# charging_block.net
KiCad netlist of a schematic drawn in EAGLE
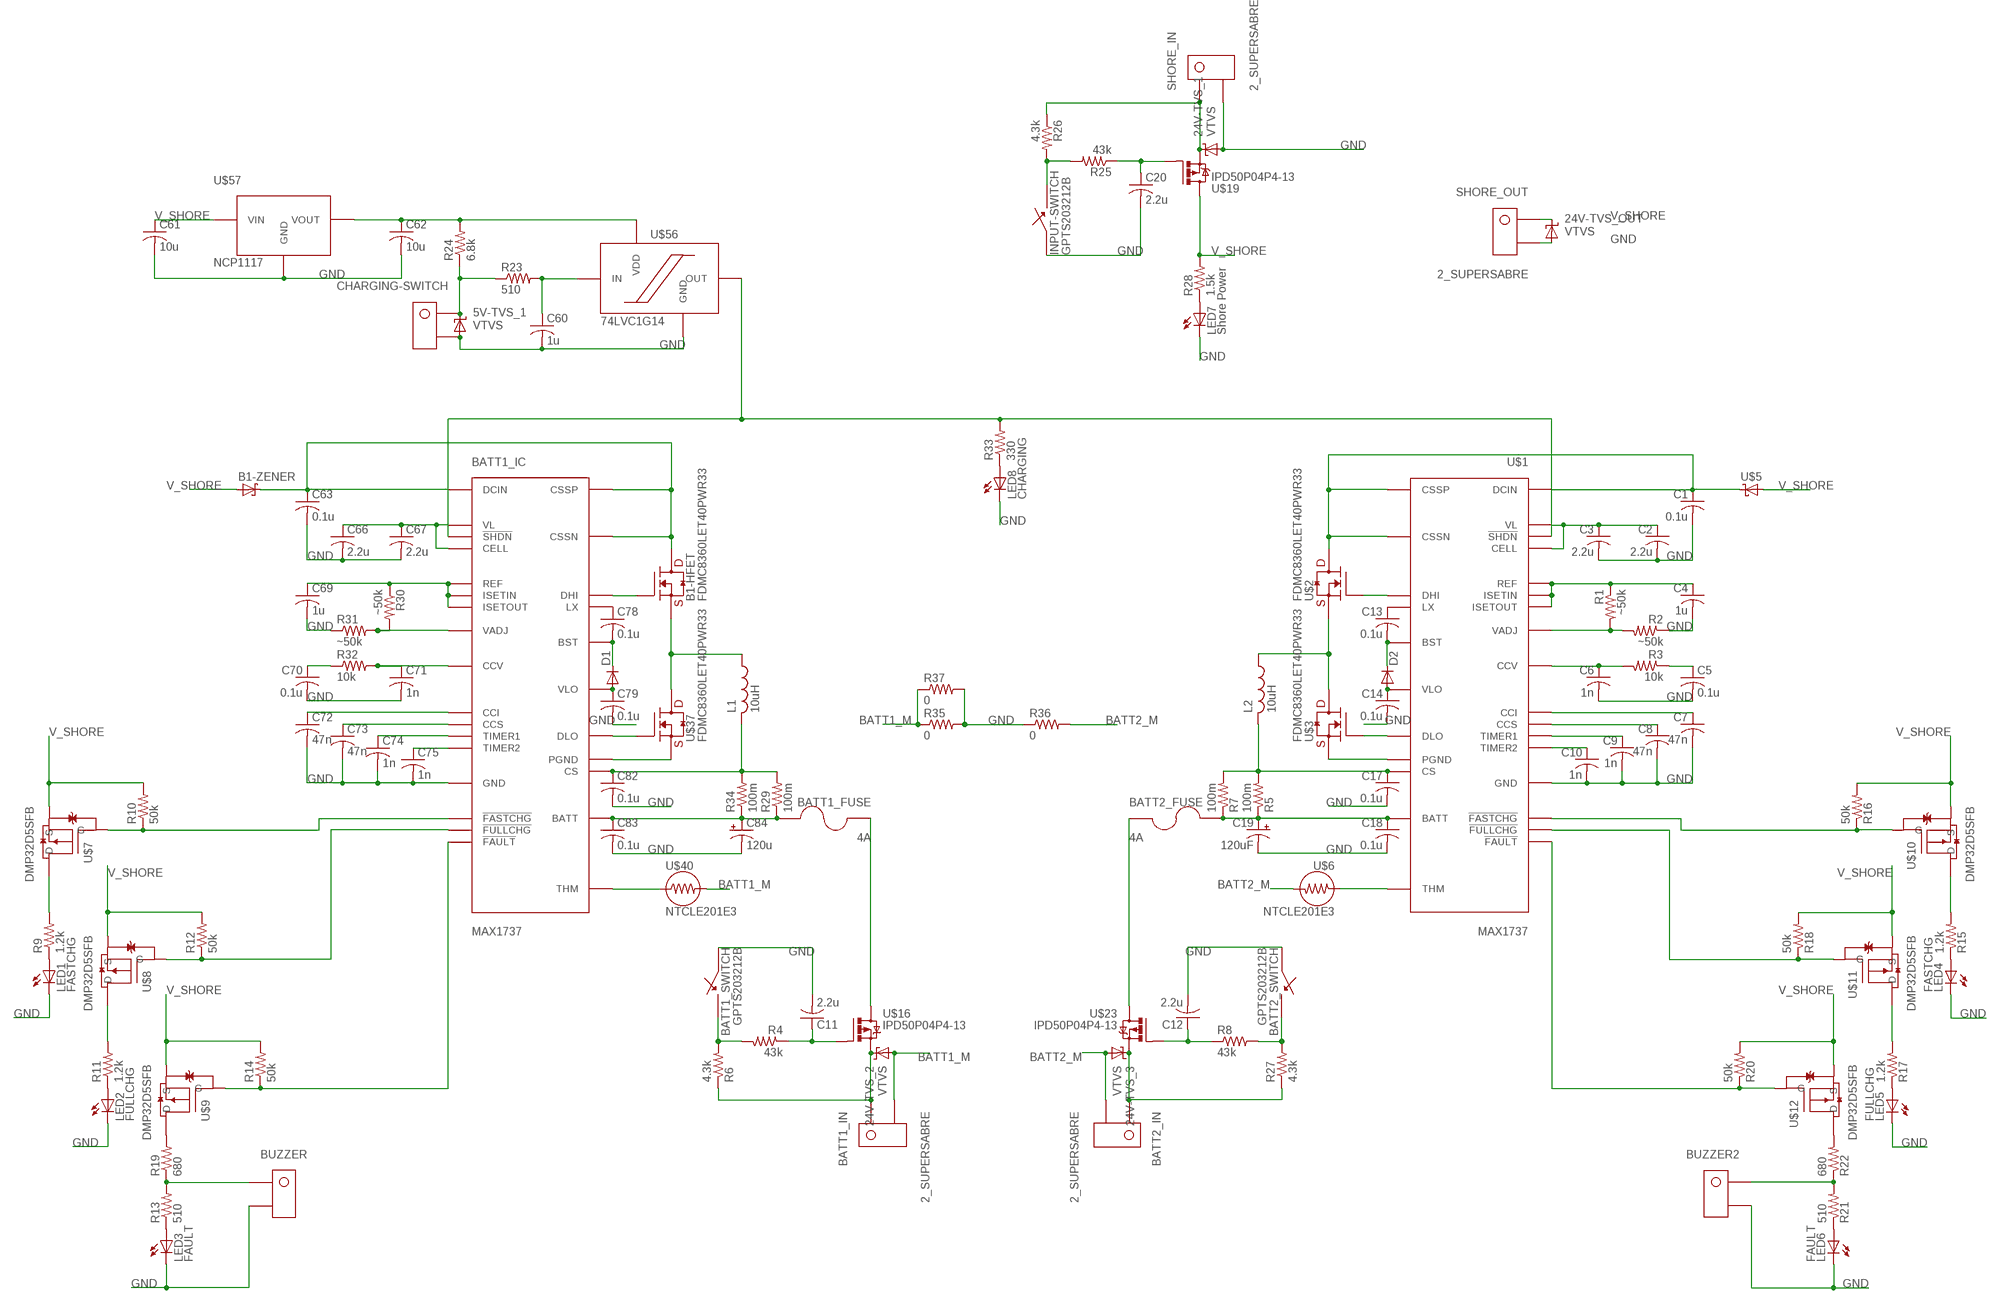
[diagram p0: schematic, sheet 1]

(export (version "E")
  (design (tool "Eeschema 10.0.6"))
  (components
    (comp (ref "5V-TVS_1")
      (value "VTVS")
      (footprint "eagle-import:DO-219AB")
      (libsource (lib "eagle-import") (part "VTVS"))
    )
    (comp (ref "24V-TVS_1")
      (value "VTVS")
      (footprint "eagle-import:DO-219AB")
      (libsource (lib "eagle-import") (part "VTVS"))
    )
    (comp (ref "24V-TVS_2")
      (value "VTVS")
      (footprint "eagle-import:DO-219AB")
      (libsource (lib "eagle-import") (part "VTVS"))
    )
    (comp (ref "24V-TVS_3")
      (value "VTVS")
      (footprint "eagle-import:DO-219AB")
      (libsource (lib "eagle-import") (part "VTVS"))
    )
    (comp (ref "24V-TVS_OUT")
      (value "VTVS")
      (footprint "eagle-import:DO-219AB")
      (libsource (lib "eagle-import") (part "VTVS"))
    )
    (comp (ref "B1-HFET")
      (value "FDMC8360LET40PWR33")
      (footprint "eagle-import:POWER33")
      (libsource (lib "eagle-import") (part "FDMC8360LET40PWR33"))
    )
    (comp (ref "B1-ZENER")
      (value "SCHOTTKY-DIODESOD-106")
      (footprint "eagle-import:SOD106-R")
      (libsource (lib "eagle-import") (part "SCHOTTKY-DIODESOD-106"))
    )
    (comp (ref "BATT1_FUSE")
      (value "4A")
      (footprint "eagle-import:154-OMNI-BLOK")
      (libsource (lib "eagle-import") (part "154-OMNI_BLOK"))
    )
    (comp (ref "BATT1_IC")
      (value "MAX1737")
      (footprint "eagle-import:QSOP28")
      (libsource (lib "eagle-import") (part "MAX1737"))
    )
    (comp (ref "BATT1_IN")
      (value "2_SUPERSABRE")
      (footprint "eagle-import:SUPERSABRE_2CIRCUIT")
      (libsource (lib "eagle-import") (part "2_SUPERSABRE"))
    )
    (comp (ref "BATT1_SWITCH")
      (value "GPTS203212B")
      (footprint "eagle-import:GPTS203211B")
      (libsource (lib "eagle-import") (part "GPTS203212B"))
    )
    (comp (ref "BATT2_FUSE")
      (value "4A")
      (footprint "eagle-import:154-OMNI-BLOK")
      (libsource (lib "eagle-import") (part "154-OMNI_BLOK"))
    )
    (comp (ref "BATT2_IN")
      (value "2_SUPERSABRE")
      (footprint "eagle-import:SUPERSABRE_2CIRCUIT")
      (libsource (lib "eagle-import") (part "2_SUPERSABRE"))
    )
    (comp (ref "BATT2_SWITCH")
      (value "GPTS203212B")
      (footprint "eagle-import:GPTS203211B")
      (libsource (lib "eagle-import") (part "GPTS203212B"))
    )
    (comp (ref "BUZZER")
      (value "KK254_VERT_2PIN22-29-2021")
      (footprint "eagle-import:KK254_VERT_2PIN")
      (libsource (lib "eagle-import") (part "KK254_VERT_2PIN22-29-2021"))
    )
    (comp (ref "BUZZER2")
      (value "KK254_VERT_2PIN22-29-2021")
      (footprint "eagle-import:KK254_VERT_2PIN")
      (libsource (lib "eagle-import") (part "KK254_VERT_2PIN22-29-2021"))
    )
    (comp (ref "C1")
      (value "0.1u")
      (footprint "eagle-import:C0805")
      (libsource (lib "eagle-import") (part "C-USC0805"))
    )
    (comp (ref "C2")
      (value "2.2u")
      (footprint "eagle-import:C0805")
      (libsource (lib "eagle-import") (part "C-USC0805"))
    )
    (comp (ref "C3")
      (value "2.2u")
      (footprint "eagle-import:C0805")
      (libsource (lib "eagle-import") (part "C-USC0805"))
    )
    (comp (ref "C4")
      (value "1u")
      (footprint "eagle-import:C0805")
      (libsource (lib "eagle-import") (part "C-USC0805"))
    )
    (comp (ref "C5")
      (value "0.1u")
      (footprint "eagle-import:C0805")
      (libsource (lib "eagle-import") (part "C-USC0805"))
    )
    (comp (ref "C6")
      (value "1n")
      (footprint "eagle-import:C0805")
      (libsource (lib "eagle-import") (part "C-USC0805"))
    )
    (comp (ref "C7")
      (value "47n")
      (footprint "eagle-import:C0805")
      (libsource (lib "eagle-import") (part "C-USC0805"))
    )
    (comp (ref "C8")
      (value "47n")
      (footprint "eagle-import:C0805")
      (libsource (lib "eagle-import") (part "C-USC0805"))
    )
    (comp (ref "C9")
      (value "1n")
      (footprint "eagle-import:C0805")
      (libsource (lib "eagle-import") (part "C-USC0805"))
    )
    (comp (ref "C10")
      (value "1n")
      (footprint "eagle-import:C0805")
      (libsource (lib "eagle-import") (part "C-USC0805"))
    )
    (comp (ref "C11")
      (value "2.2u")
      (footprint "eagle-import:C0805")
      (libsource (lib "eagle-import") (part "C-USC0805"))
    )
    (comp (ref "C12")
      (value "2.2u")
      (footprint "eagle-import:C0805")
      (libsource (lib "eagle-import") (part "C-USC0805"))
    )
    (comp (ref "C13")
      (value "0.1u")
      (footprint "eagle-import:C0805")
      (libsource (lib "eagle-import") (part "C-USC0805"))
    )
    (comp (ref "C14")
      (value "0.1u")
      (footprint "eagle-import:C0805")
      (libsource (lib "eagle-import") (part "C-USC0805"))
    )
    (comp (ref "C17")
      (value "0.1u")
      (footprint "eagle-import:C0805")
      (libsource (lib "eagle-import") (part "C-USC0805"))
    )
    (comp (ref "C18")
      (value "0.1u")
      (footprint "eagle-import:C0805")
      (libsource (lib "eagle-import") (part "C-USC0805"))
    )
    (comp (ref "C19")
      (value "120uF")
      (footprint "eagle-import:E3,5-8")
      (libsource (lib "eagle-import") (part "CPOL-USE3.5-8"))
    )
    (comp (ref "C20")
      (value "2.2u")
      (footprint "eagle-import:C0805")
      (libsource (lib "eagle-import") (part "C-USC0805"))
    )
    (comp (ref "C60")
      (value "1u")
      (footprint "eagle-import:C0805")
      (libsource (lib "eagle-import") (part "C-USC0805"))
    )
    (comp (ref "C61")
      (value "10u")
      (footprint "eagle-import:C0805")
      (libsource (lib "eagle-import") (part "C-USC0805"))
    )
    (comp (ref "C62")
      (value "10u")
      (footprint "eagle-import:C0805")
      (libsource (lib "eagle-import") (part "C-USC0805"))
    )
    (comp (ref "C63")
      (value "0.1u")
      (footprint "eagle-import:C0805")
      (libsource (lib "eagle-import") (part "C-USC0805"))
    )
    (comp (ref "C66")
      (value "2.2u")
      (footprint "eagle-import:C0805")
      (libsource (lib "eagle-import") (part "C-USC0805"))
    )
    (comp (ref "C67")
      (value "2.2u")
      (footprint "eagle-import:C0805")
      (libsource (lib "eagle-import") (part "C-USC0805"))
    )
    (comp (ref "C69")
      (value "1u")
      (footprint "eagle-import:C0805")
      (libsource (lib "eagle-import") (part "C-USC0805"))
    )
    (comp (ref "C70")
      (value "0.1u")
      (footprint "eagle-import:C0805")
      (libsource (lib "eagle-import") (part "C-USC0805"))
    )
    (comp (ref "C71")
      (value "1n")
      (footprint "eagle-import:C0805")
      (libsource (lib "eagle-import") (part "C-USC0805"))
    )
    (comp (ref "C72")
      (value "47n")
      (footprint "eagle-import:C0805")
      (libsource (lib "eagle-import") (part "C-USC0805"))
    )
    (comp (ref "C73")
      (value "47n")
      (footprint "eagle-import:C0805")
      (libsource (lib "eagle-import") (part "C-USC0805"))
    )
    (comp (ref "C74")
      (value "1n")
      (footprint "eagle-import:C0805")
      (libsource (lib "eagle-import") (part "C-USC0805"))
    )
    (comp (ref "C75")
      (value "1n")
      (footprint "eagle-import:C0805")
      (libsource (lib "eagle-import") (part "C-USC0805"))
    )
    (comp (ref "C78")
      (value "0.1u")
      (footprint "eagle-import:C0805")
      (libsource (lib "eagle-import") (part "C-USC0805"))
    )
    (comp (ref "C79")
      (value "0.1u")
      (footprint "eagle-import:C0805")
      (libsource (lib "eagle-import") (part "C-USC0805"))
    )
    (comp (ref "C82")
      (value "0.1u")
      (footprint "eagle-import:C0805")
      (libsource (lib "eagle-import") (part "C-USC0805"))
    )
    (comp (ref "C83")
      (value "0.1u")
      (footprint "eagle-import:C0805")
      (libsource (lib "eagle-import") (part "C-USC0805"))
    )
    (comp (ref "C84")
      (value "120u")
      (footprint "eagle-import:E3,5-8")
      (libsource (lib "eagle-import") (part "CPOL-USE3.5-8"))
    )
    (comp (ref "CHARGING-SWITCH")
      (value "KK254_VERT_2PIN22-29-2021")
      (footprint "eagle-import:KK254_VERT_2PIN")
      (libsource (lib "eagle-import") (part "KK254_VERT_2PIN22-29-2021"))
    )
    (comp (ref "D1")
      (value "DIODE-SOD123")
      (footprint "eagle-import:SOD123")
      (libsource (lib "eagle-import") (part "DIODE-SOD123"))
    )
    (comp (ref "D2")
      (value "DIODE-SOD123")
      (footprint "eagle-import:SOD123")
      (libsource (lib "eagle-import") (part "DIODE-SOD123"))
    )
    (comp (ref "INPUT-SWITCH")
      (value "GPTS203212B")
      (footprint "eagle-import:GPTS203211B")
      (libsource (lib "eagle-import") (part "GPTS203212B"))
    )
    (comp (ref "L1")
      (value "10uH")
      (footprint "eagle-import:L6100")
      (libsource (lib "eagle-import") (part "L-USL6100"))
    )
    (comp (ref "L2")
      (value "10uH")
      (footprint "eagle-import:L6100")
      (libsource (lib "eagle-import") (part "L-USL6100"))
    )
    (comp (ref "LED1")
      (value "FASTCHG")
      (footprint "eagle-import:CHIP-LED0805")
      (libsource (lib "eagle-import") (part "LEDCHIP-LED0805"))
    )
    (comp (ref "LED2")
      (value "FULLCHG")
      (footprint "eagle-import:CHIP-LED0805")
      (libsource (lib "eagle-import") (part "LEDCHIP-LED0805"))
    )
    (comp (ref "LED3")
      (value "FAULT")
      (footprint "eagle-import:CHIP-LED0805")
      (libsource (lib "eagle-import") (part "LEDCHIP-LED0805"))
    )
    (comp (ref "LED4")
      (value "FASTCHG")
      (footprint "eagle-import:CHIP-LED0805")
      (libsource (lib "eagle-import") (part "LEDCHIP-LED0805"))
    )
    (comp (ref "LED5")
      (value "FULLCHG")
      (footprint "eagle-import:CHIP-LED0805")
      (libsource (lib "eagle-import") (part "LEDCHIP-LED0805"))
    )
    (comp (ref "LED6")
      (value "FAULT")
      (footprint "eagle-import:CHIP-LED0805")
      (libsource (lib "eagle-import") (part "LEDCHIP-LED0805"))
    )
    (comp (ref "LED7")
      (value "Shore Power")
      (footprint "eagle-import:CHIP-LED0805")
      (libsource (lib "eagle-import") (part "LEDCHIP-LED0805"))
    )
    (comp (ref "LED8")
      (value "CHARGING")
      (footprint "eagle-import:CHIP-LED0805")
      (libsource (lib "eagle-import") (part "LEDCHIP-LED0805"))
    )
    (comp (ref "R1")
      (value "~50k")
      (footprint "eagle-import:R0805")
      (libsource (lib "eagle-import") (part "R-US_R0805"))
    )
    (comp (ref "R2")
      (value "~50k")
      (footprint "eagle-import:R0805")
      (libsource (lib "eagle-import") (part "R-US_R0805"))
    )
    (comp (ref "R3")
      (value "10k")
      (footprint "eagle-import:R0805")
      (libsource (lib "eagle-import") (part "R-US_R0805"))
    )
    (comp (ref "R4")
      (value "43k")
      (footprint "eagle-import:R0805")
      (libsource (lib "eagle-import") (part "R-US_R0805"))
    )
    (comp (ref "R5")
      (value "100m")
      (footprint "eagle-import:R2512")
      (libsource (lib "eagle-import") (part "R-US_R2512"))
    )
    (comp (ref "R6")
      (value "4.3k")
      (footprint "eagle-import:R0805")
      (libsource (lib "eagle-import") (part "R-US_R0805"))
    )
    (comp (ref "R7")
      (value "100m")
      (footprint "eagle-import:R2512")
      (libsource (lib "eagle-import") (part "R-US_R2512"))
    )
    (comp (ref "R8")
      (value "43k")
      (footprint "eagle-import:R0805")
      (libsource (lib "eagle-import") (part "R-US_R0805"))
    )
    (comp (ref "R9")
      (value "1.2k")
      (footprint "eagle-import:R0805")
      (libsource (lib "eagle-import") (part "R-US_R0805"))
    )
    (comp (ref "R10")
      (value "50k")
      (footprint "eagle-import:R0805")
      (libsource (lib "eagle-import") (part "R-US_R0805"))
    )
    (comp (ref "R11")
      (value "1.2k")
      (footprint "eagle-import:R0805")
      (libsource (lib "eagle-import") (part "R-US_R0805"))
    )
    (comp (ref "R12")
      (value "50k")
      (footprint "eagle-import:R0805")
      (libsource (lib "eagle-import") (part "R-US_R0805"))
    )
    (comp (ref "R13")
      (value "510")
      (footprint "eagle-import:R0805")
      (libsource (lib "eagle-import") (part "R-US_R0805"))
    )
    (comp (ref "R14")
      (value "50k")
      (footprint "eagle-import:R0805")
      (libsource (lib "eagle-import") (part "R-US_R0805"))
    )
    (comp (ref "R15")
      (value "1.2k")
      (footprint "eagle-import:R0805")
      (libsource (lib "eagle-import") (part "R-US_R0805"))
    )
    (comp (ref "R16")
      (value "50k")
      (footprint "eagle-import:R0805")
      (libsource (lib "eagle-import") (part "R-US_R0805"))
    )
    (comp (ref "R17")
      (value "1.2k")
      (footprint "eagle-import:R0805")
      (libsource (lib "eagle-import") (part "R-US_R0805"))
    )
    (comp (ref "R18")
      (value "50k")
      (footprint "eagle-import:R0805")
      (libsource (lib "eagle-import") (part "R-US_R0805"))
    )
    (comp (ref "R19")
      (value "680")
      (footprint "eagle-import:R0805")
      (libsource (lib "eagle-import") (part "R-US_R0805"))
    )
    (comp (ref "R20")
      (value "50k")
      (footprint "eagle-import:R0805")
      (libsource (lib "eagle-import") (part "R-US_R0805"))
    )
    (comp (ref "R21")
      (value "510")
      (footprint "eagle-import:R0805")
      (libsource (lib "eagle-import") (part "R-US_R0805"))
    )
    (comp (ref "R22")
      (value "680")
      (footprint "eagle-import:R0805")
      (libsource (lib "eagle-import") (part "R-US_R0805"))
    )
    (comp (ref "R23")
      (value "510")
      (footprint "eagle-import:R0805")
      (libsource (lib "eagle-import") (part "R-US_R0805"))
    )
    (comp (ref "R24")
      (value "6.8k")
      (footprint "eagle-import:R0805")
      (libsource (lib "eagle-import") (part "R-US_R0805"))
    )
    (comp (ref "R25")
      (value "43k")
      (footprint "eagle-import:R0805")
      (libsource (lib "eagle-import") (part "R-US_R0805"))
    )
    (comp (ref "R26")
      (value "4.3k")
      (footprint "eagle-import:R0805")
      (libsource (lib "eagle-import") (part "R-US_R0805"))
    )
    (comp (ref "R27")
      (value "4.3k")
      (footprint "eagle-import:R0805")
      (libsource (lib "eagle-import") (part "R-US_R0805"))
    )
    (comp (ref "R28")
      (value "1.5k")
      (footprint "eagle-import:R0805")
      (libsource (lib "eagle-import") (part "R-US_R0805"))
    )
    (comp (ref "R29")
      (value "100m")
      (footprint "eagle-import:R2512")
      (libsource (lib "eagle-import") (part "R-US_R2512"))
    )
    (comp (ref "R30")
      (value "~50k")
      (footprint "eagle-import:R0805")
      (libsource (lib "eagle-import") (part "R-US_R0805"))
    )
    (comp (ref "R31")
      (value "~50k")
      (footprint "eagle-import:R0805")
      (libsource (lib "eagle-import") (part "R-US_R0805"))
    )
    (comp (ref "R32")
      (value "10k")
      (footprint "eagle-import:R0805")
      (libsource (lib "eagle-import") (part "R-US_R0805"))
    )
    (comp (ref "R33")
      (value "330")
      (footprint "eagle-import:R0805")
      (libsource (lib "eagle-import") (part "R-US_R0805"))
    )
    (comp (ref "R34")
      (value "100m")
      (footprint "eagle-import:R2512")
      (libsource (lib "eagle-import") (part "R-US_R2512"))
    )
    (comp (ref "R35")
      (value "0")
      (footprint "eagle-import:R0805")
      (libsource (lib "eagle-import") (part "R-US_R0805"))
    )
    (comp (ref "R36")
      (value "0")
      (footprint "eagle-import:R0805")
      (libsource (lib "eagle-import") (part "R-US_R0805"))
    )
    (comp (ref "R37")
      (value "0")
      (footprint "eagle-import:R0805")
      (libsource (lib "eagle-import") (part "R-US_R0805"))
    )
    (comp (ref "SHORE_IN")
      (value "2_SUPERSABRE")
      (footprint "eagle-import:SUPERSABRE_2CIRCUIT")
      (libsource (lib "eagle-import") (part "2_SUPERSABRE"))
    )
    (comp (ref "SHORE_OUT")
      (value "2_SUPERSABRE")
      (footprint "eagle-import:SUPERSABRE_2CIRCUIT")
      (libsource (lib "eagle-import") (part "2_SUPERSABRE"))
    )
    (comp (ref "U$1")
      (value "MAX1737")
      (footprint "eagle-import:QSOP28")
      (libsource (lib "eagle-import") (part "MAX1737"))
    )
    (comp (ref "U$2")
      (value "FDMC8360LET40PWR33")
      (footprint "eagle-import:POWER33")
      (libsource (lib "eagle-import") (part "FDMC8360LET40PWR33"))
    )
    (comp (ref "U$3")
      (value "FDMC8360LET40PWR33")
      (footprint "eagle-import:POWER33")
      (libsource (lib "eagle-import") (part "FDMC8360LET40PWR33"))
    )
    (comp (ref "U$5")
      (value "SCHOTTKY-DIODESOD-106")
      (footprint "eagle-import:SOD106-R")
      (libsource (lib "eagle-import") (part "SCHOTTKY-DIODESOD-106"))
    )
    (comp (ref "U$6")
      (value "NTCLE201E3")
      (footprint "eagle-import:2-0.3MM-LEADS")
      (libsource (lib "eagle-import") (part "NTCLE201E3"))
    )
    (comp (ref "U$7")
      (value "DMP32D5SFB")
      (footprint "eagle-import:AP02002")
      (libsource (lib "eagle-import") (part "DMP32D5SFB"))
    )
    (comp (ref "U$8")
      (value "DMP32D5SFB")
      (footprint "eagle-import:AP02002")
      (libsource (lib "eagle-import") (part "DMP32D5SFB"))
    )
    (comp (ref "U$9")
      (value "DMP32D5SFB")
      (footprint "eagle-import:AP02002")
      (libsource (lib "eagle-import") (part "DMP32D5SFB"))
    )
    (comp (ref "U$10")
      (value "DMP32D5SFB")
      (footprint "eagle-import:AP02002")
      (libsource (lib "eagle-import") (part "DMP32D5SFB"))
    )
    (comp (ref "U$11")
      (value "DMP32D5SFB")
      (footprint "eagle-import:AP02002")
      (libsource (lib "eagle-import") (part "DMP32D5SFB"))
    )
    (comp (ref "U$12")
      (value "DMP32D5SFB")
      (footprint "eagle-import:AP02002")
      (libsource (lib "eagle-import") (part "DMP32D5SFB"))
    )
    (comp (ref "U$16")
      (value "IPD50P04P4-13")
      (footprint "eagle-import:TO252-3")
      (libsource (lib "eagle-import") (part "IPD50P04P4-13"))
    )
    (comp (ref "U$19")
      (value "IPD50P04P4-13")
      (footprint "eagle-import:TO252-3")
      (libsource (lib "eagle-import") (part "IPD50P04P4-13"))
    )
    (comp (ref "U$23")
      (value "IPD50P04P4-13")
      (footprint "eagle-import:TO252-3")
      (libsource (lib "eagle-import") (part "IPD50P04P4-13"))
    )
    (comp (ref "U$37")
      (value "FDMC8360LET40PWR33")
      (footprint "eagle-import:POWER33")
      (libsource (lib "eagle-import") (part "FDMC8360LET40PWR33"))
    )
    (comp (ref "U$40")
      (value "NTCLE201E3")
      (footprint "eagle-import:2-0.3MM-LEADS")
      (libsource (lib "eagle-import") (part "NTCLE201E3"))
    )
    (comp (ref "U$56")
      (value "74LVC1G14")
      (footprint "eagle-import:TSSOP5")
      (libsource (lib "eagle-import") (part "74LVC1G14"))
    )
    (comp (ref "U$57")
      (value "NCP1117")
      (footprint "eagle-import:SOT-223")
      (libsource (lib "eagle-import") (part "NCP1117"))
    )
  )
  (nets
    (net (code "1") (name "/BATT1_M") (class "Default")
      (node (ref "24V-TVS_2") (pin "P$1") (pinfunction "A_P$1") (pintype "passive"))
      (node (ref "BATT1_IN") (pin "P$2") (pinfunction "P$2_P$2") (pintype "bidirectional"))
      (node (ref "R35") (pin "1") (pinfunction "1_1") (pintype "passive"))
      (node (ref "R37") (pin "1") (pinfunction "1_1") (pintype "passive"))
      (node (ref "U$40") (pin "P$2") (pinfunction "2_P$2") (pintype "passive"))
    )
    (net (code "2") (name "/BATT2_M") (class "Default")
      (node (ref "24V-TVS_3") (pin "P$1") (pinfunction "A_P$1") (pintype "passive"))
      (node (ref "BATT2_IN") (pin "P$2") (pinfunction "P$2_P$2") (pintype "bidirectional"))
      (node (ref "R36") (pin "2") (pinfunction "2_2") (pintype "passive"))
      (node (ref "U$6") (pin "P$2") (pinfunction "2_P$2") (pintype "passive"))
    )
    (net (code "3") (name "/GND") (class "Default")
      (node (ref "24V-TVS_1") (pin "P$1") (pinfunction "A_P$1") (pintype "passive"))
      (node (ref "24V-TVS_OUT") (pin "P$1") (pinfunction "A_P$1") (pintype "passive"))
      (node (ref "5V-TVS_1") (pin "P$1") (pinfunction "A_P$1") (pintype "passive"))
      (node (ref "BATT1_IC") (pin "6") (pinfunction "GND_6") (pintype "bidirectional"))
      (node (ref "BATT1_SWITCH") (pin "P$1") (pinfunction "P$1_P$1") (pintype "bidirectional"))
      (node (ref "BATT2_SWITCH") (pin "P$1") (pinfunction "P$1_P$1") (pintype "bidirectional"))
      (node (ref "BUZZER") (pin "P$2") (pinfunction "P$2_P$2") (pintype "bidirectional"))
      (node (ref "BUZZER2") (pin "P$2") (pinfunction "P$2_P$2") (pintype "bidirectional"))
      (node (ref "C1") (pin "2") (pinfunction "2_2") (pintype "passive"))
      (node (ref "C10") (pin "2") (pinfunction "2_2") (pintype "passive"))
      (node (ref "C11") (pin "2") (pinfunction "2_2") (pintype "passive"))
      (node (ref "C12") (pin "2") (pinfunction "2_2") (pintype "passive"))
      (node (ref "C14") (pin "2") (pinfunction "2_2") (pintype "passive"))
      (node (ref "C17") (pin "2") (pinfunction "2_2") (pintype "passive"))
      (node (ref "C18") (pin "2") (pinfunction "2_2") (pintype "passive"))
      (node (ref "C19") (pin "-") (pinfunction "-_-") (pintype "passive"))
      (node (ref "C2") (pin "2") (pinfunction "2_2") (pintype "passive"))
      (node (ref "C20") (pin "2") (pinfunction "2_2") (pintype "passive"))
      (node (ref "C3") (pin "2") (pinfunction "2_2") (pintype "passive"))
      (node (ref "C4") (pin "2") (pinfunction "2_2") (pintype "passive"))
      (node (ref "C5") (pin "2") (pinfunction "2_2") (pintype "passive"))
      (node (ref "C6") (pin "2") (pinfunction "2_2") (pintype "passive"))
      (node (ref "C60") (pin "2") (pinfunction "2_2") (pintype "passive"))
      (node (ref "C61") (pin "2") (pinfunction "2_2") (pintype "passive"))
      (node (ref "C62") (pin "2") (pinfunction "2_2") (pintype "passive"))
      (node (ref "C63") (pin "2") (pinfunction "2_2") (pintype "passive"))
      (node (ref "C66") (pin "2") (pinfunction "2_2") (pintype "passive"))
      (node (ref "C67") (pin "2") (pinfunction "2_2") (pintype "passive"))
      (node (ref "C69") (pin "2") (pinfunction "2_2") (pintype "passive"))
      (node (ref "C7") (pin "2") (pinfunction "2_2") (pintype "passive"))
      (node (ref "C70") (pin "2") (pinfunction "2_2") (pintype "passive"))
      (node (ref "C71") (pin "2") (pinfunction "2_2") (pintype "passive"))
      (node (ref "C72") (pin "2") (pinfunction "2_2") (pintype "passive"))
      (node (ref "C73") (pin "2") (pinfunction "2_2") (pintype "passive"))
      (node (ref "C74") (pin "2") (pinfunction "2_2") (pintype "passive"))
      (node (ref "C75") (pin "2") (pinfunction "2_2") (pintype "passive"))
      (node (ref "C79") (pin "2") (pinfunction "2_2") (pintype "passive"))
      (node (ref "C8") (pin "2") (pinfunction "2_2") (pintype "passive"))
      (node (ref "C82") (pin "2") (pinfunction "2_2") (pintype "passive"))
      (node (ref "C83") (pin "2") (pinfunction "2_2") (pintype "passive"))
      (node (ref "C84") (pin "-") (pinfunction "-_-") (pintype "passive"))
      (node (ref "C9") (pin "2") (pinfunction "2_2") (pintype "passive"))
      (node (ref "CHARGING-SWITCH") (pin "P$2") (pinfunction "P$2_P$2") (pintype "bidirectional"))
      (node (ref "INPUT-SWITCH") (pin "P$1") (pinfunction "P$1_P$1") (pintype "bidirectional"))
      (node (ref "LED1") (pin "C") (pinfunction "C_C") (pintype "passive"))
      (node (ref "LED2") (pin "C") (pinfunction "C_C") (pintype "passive"))
      (node (ref "LED3") (pin "C") (pinfunction "C_C") (pintype "passive"))
      (node (ref "LED4") (pin "C") (pinfunction "C_C") (pintype "passive"))
      (node (ref "LED5") (pin "C") (pinfunction "C_C") (pintype "passive"))
      (node (ref "LED6") (pin "C") (pinfunction "C_C") (pintype "passive"))
      (node (ref "LED7") (pin "C") (pinfunction "C_C") (pintype "passive"))
      (node (ref "LED8") (pin "C") (pinfunction "C_C") (pintype "passive"))
      (node (ref "R2") (pin "1") (pinfunction "1_1") (pintype "passive"))
      (node (ref "R31") (pin "1") (pinfunction "1_1") (pintype "passive"))
      (node (ref "R35") (pin "2") (pinfunction "2_2") (pintype "passive"))
      (node (ref "R36") (pin "1") (pinfunction "1_1") (pintype "passive"))
      (node (ref "R37") (pin "2") (pinfunction "2_2") (pintype "passive"))
      (node (ref "SHORE_IN") (pin "P$2") (pinfunction "P$2_P$2") (pintype "bidirectional"))
      (node (ref "SHORE_OUT") (pin "P$2") (pinfunction "P$2_P$2") (pintype "bidirectional"))
      (node (ref "U$1") (pin "6") (pinfunction "GND_6") (pintype "bidirectional"))
      (node (ref "U$56") (pin "P$3") (pinfunction "GND_P$3") (pintype "bidirectional"))
      (node (ref "U$57") (pin "P$1") (pinfunction "GND_P$1") (pintype "bidirectional"))
    )
    (net (code "4") (name "/V_SHORE") (class "Default")
      (node (ref "24V-TVS_OUT") (pin "P$2") (pinfunction "C_P$2") (pintype "passive"))
      (node (ref "B1-ZENER") (pin "A") (pinfunction "A_A") (pintype "passive"))
      (node (ref "C61") (pin "1") (pinfunction "1_1") (pintype "passive"))
      (node (ref "R10") (pin "2") (pinfunction "2_2") (pintype "passive"))
      (node (ref "R12") (pin "2") (pinfunction "2_2") (pintype "passive"))
      (node (ref "R14") (pin "2") (pinfunction "2_2") (pintype "passive"))
      (node (ref "R16") (pin "2") (pinfunction "2_2") (pintype "passive"))
      (node (ref "R18") (pin "2") (pinfunction "2_2") (pintype "passive"))
      (node (ref "R20") (pin "2") (pinfunction "2_2") (pintype "passive"))
      (node (ref "R28") (pin "2") (pinfunction "2_2") (pintype "passive"))
      (node (ref "SHORE_OUT") (pin "P$1") (pinfunction "P$1_P$1") (pintype "bidirectional"))
      (node (ref "U$10") (pin "P$1") (pinfunction "S_P$1") (pintype "bidirectional"))
      (node (ref "U$11") (pin "P$1") (pinfunction "S_P$1") (pintype "bidirectional"))
      (node (ref "U$12") (pin "P$1") (pinfunction "S_P$1") (pintype "bidirectional"))
      (node (ref "U$19") (pin "3") (pinfunction "S_3") (pintype "passive"))
      (node (ref "U$5") (pin "A") (pinfunction "A_A") (pintype "passive"))
      (node (ref "U$57") (pin "P$3") (pinfunction "VIN_P$3") (pintype "bidirectional"))
      (node (ref "U$7") (pin "P$1") (pinfunction "S_P$1") (pintype "bidirectional"))
      (node (ref "U$8") (pin "P$1") (pinfunction "S_P$1") (pintype "bidirectional"))
      (node (ref "U$9") (pin "P$1") (pinfunction "S_P$1") (pintype "bidirectional"))
    )
    (net (code "5") (name "Net-(5V-TVS_1-C)") (class "Default")
      (node (ref "5V-TVS_1") (pin "P$2") (pinfunction "C_P$2") (pintype "passive"))
      (node (ref "CHARGING-SWITCH") (pin "P$1") (pinfunction "P$1_P$1") (pintype "bidirectional"))
      (node (ref "R23") (pin "1") (pinfunction "1_1") (pintype "passive"))
      (node (ref "R24") (pin "1") (pinfunction "1_1") (pintype "passive"))
    )
    (net (code "6") (name "Net-(24V-TVS_1-C)") (class "Default")
      (node (ref "24V-TVS_1") (pin "P$2") (pinfunction "C_P$2") (pintype "passive"))
      (node (ref "R26") (pin "1") (pinfunction "1_1") (pintype "passive"))
      (node (ref "SHORE_IN") (pin "P$1") (pinfunction "P$1_P$1") (pintype "bidirectional"))
      (node (ref "U$19") (pin "TAB") (pinfunction "D_TAB") (pintype "passive"))
    )
    (net (code "7") (name "Net-(24V-TVS_2-C)") (class "Default")
      (node (ref "24V-TVS_2") (pin "P$2") (pinfunction "C_P$2") (pintype "passive"))
      (node (ref "BATT1_IN") (pin "P$1") (pinfunction "P$1_P$1") (pintype "bidirectional"))
      (node (ref "R6") (pin "1") (pinfunction "1_1") (pintype "passive"))
      (node (ref "U$16") (pin "TAB") (pinfunction "D_TAB") (pintype "passive"))
    )
    (net (code "8") (name "Net-(24V-TVS_3-C)") (class "Default")
      (node (ref "24V-TVS_3") (pin "P$2") (pinfunction "C_P$2") (pintype "passive"))
      (node (ref "BATT2_IN") (pin "P$1") (pinfunction "P$1_P$1") (pintype "bidirectional"))
      (node (ref "R27") (pin "1") (pinfunction "1_1") (pintype "passive"))
      (node (ref "U$23") (pin "TAB") (pinfunction "D_TAB") (pintype "passive"))
    )
    (net (code "9") (name "Net-(BATT1_IC-BATT)") (class "Default")
      (node (ref "BATT1_FUSE") (pin "P$2") (pinfunction "P$2_P$2") (pintype "bidirectional"))
      (node (ref "BATT1_IC") (pin "7") (pinfunction "BATT_7") (pintype "bidirectional"))
      (node (ref "C83") (pin "1") (pinfunction "1_1") (pintype "passive"))
      (node (ref "C84") (pin "+") (pinfunction "+_+") (pintype "passive"))
      (node (ref "R29") (pin "1") (pinfunction "1_1") (pintype "passive"))
      (node (ref "R34") (pin "1") (pinfunction "1_1") (pintype "passive"))
    )
    (net (code "10") (name "Net-(BATT1_IC-BST)") (class "Default")
      (node (ref "BATT1_IC") (pin "23") (pinfunction "BST_23") (pintype "bidirectional"))
      (node (ref "C78") (pin "2") (pinfunction "2_2") (pintype "passive"))
      (node (ref "D1") (pin "C") (pinfunction "C_C") (pintype "passive"))
    )
    (net (code "11") (name "Net-(BATT1_IC-CCI)") (class "Default")
      (node (ref "BATT1_IC") (pin "11") (pinfunction "CCI_11") (pintype "bidirectional"))
      (node (ref "C72") (pin "1") (pinfunction "1_1") (pintype "passive"))
    )
    (net (code "12") (name "Net-(BATT1_IC-CCS)") (class "Default")
      (node (ref "BATT1_IC") (pin "10") (pinfunction "CCS_10") (pintype "bidirectional"))
      (node (ref "C73") (pin "1") (pinfunction "1_1") (pintype "passive"))
    )
    (net (code "13") (name "Net-(BATT1_IC-CCV)") (class "Default")
      (node (ref "BATT1_IC") (pin "9") (pinfunction "CCV_9") (pintype "bidirectional"))
      (node (ref "C71") (pin "1") (pinfunction "1_1") (pintype "passive"))
      (node (ref "R32") (pin "2") (pinfunction "2_2") (pintype "passive"))
    )
    (net (code "14") (name "Net-(BATT1_IC-CELL)") (class "Default")
      (node (ref "BATT1_IC") (pin "1") (pinfunction "VL_1") (pintype "bidirectional"))
      (node (ref "BATT1_IC") (pin "12") (pinfunction "CELL_12") (pintype "bidirectional"))
      (node (ref "C66") (pin "1") (pinfunction "1_1") (pintype "passive"))
      (node (ref "C67") (pin "1") (pinfunction "1_1") (pintype "passive"))
    )
    (net (code "15") (name "Net-(BATT1_IC-CS)") (class "Default")
      (node (ref "BATT1_IC") (pin "19") (pinfunction "CS_19") (pintype "bidirectional"))
      (node (ref "C82") (pin "1") (pinfunction "1_1") (pintype "passive"))
      (node (ref "L1") (pin "P$2") (pinfunction "2_P$2") (pintype "passive"))
      (node (ref "R29") (pin "2") (pinfunction "2_2") (pintype "passive"))
      (node (ref "R34") (pin "2") (pinfunction "2_2") (pintype "passive"))
    )
    (net (code "16") (name "Net-(BATT1_IC-CSSN)") (class "Default")
      (node (ref "B1-HFET") (pin "DRAIN") (pinfunction "DRAIN_DRAIN") (pintype "bidirectional"))
      (node (ref "B1-ZENER") (pin "C") (pinfunction "C_C") (pintype "passive"))
      (node (ref "BATT1_IC") (pin "26") (pinfunction "CSSN_26") (pintype "bidirectional"))
      (node (ref "BATT1_IC") (pin "27") (pinfunction "CSSP_27") (pintype "bidirectional"))
      (node (ref "BATT1_IC") (pin "28") (pinfunction "DCIN_28") (pintype "bidirectional"))
      (node (ref "C63") (pin "1") (pinfunction "1_1") (pintype "passive"))
    )
    (net (code "17") (name "Net-(BATT1_IC-DHI)") (class "Default")
      (node (ref "B1-HFET") (pin "GATE") (pinfunction "GATE_GATE") (pintype "passive"))
      (node (ref "BATT1_IC") (pin "25") (pinfunction "DHI_25") (pintype "bidirectional"))
    )
    (net (code "18") (name "Net-(BATT1_IC-DLO)") (class "Default")
      (node (ref "BATT1_IC") (pin "21") (pinfunction "DLO_21") (pintype "bidirectional"))
      (node (ref "U$37") (pin "GATE") (pinfunction "GATE_GATE") (pintype "passive"))
    )
    (net (code "19") (name "Net-(BATT1_IC-ISETIN)") (class "Default")
      (node (ref "BATT1_IC") (pin "2") (pinfunction "ISETIN_2") (pintype "bidirectional"))
      (node (ref "BATT1_IC") (pin "3") (pinfunction "ISETOUT_3") (pintype "bidirectional"))
      (node (ref "BATT1_IC") (pin "5") (pinfunction "REF_5") (pintype "bidirectional"))
      (node (ref "C69") (pin "1") (pinfunction "1_1") (pintype "passive"))
      (node (ref "R30") (pin "1") (pinfunction "1_1") (pintype "passive"))
    )
    (net (code "20") (name "Net-(BATT1_IC-LX)") (class "Default")
      (node (ref "BATT1_IC") (pin "24") (pinfunction "LX_24") (pintype "bidirectional"))
      (node (ref "C78") (pin "1") (pinfunction "1_1") (pintype "passive"))
    )
    (net (code "21") (name "Net-(BATT1_IC-PGND)") (class "Default")
      (node (ref "BATT1_IC") (pin "20") (pinfunction "PGND_20") (pintype "bidirectional"))
      (node (ref "U$37") (pin "SOURCE1") (pinfunction "SOURCE_SOURCE1") (pintype "passive"))
      (node (ref "U$37") (pin "SOURCE2") (pinfunction "SOURCE_SOURCE2") (pintype "passive"))
      (node (ref "U$37") (pin "SOURCE3") (pinfunction "SOURCE_SOURCE3") (pintype "passive"))
    )
    (net (code "22") (name "Net-(BATT1_IC-THM)") (class "Default")
      (node (ref "BATT1_IC") (pin "4") (pinfunction "THM_4") (pintype "bidirectional"))
      (node (ref "U$40") (pin "P$1") (pinfunction "1_P$1") (pintype "passive"))
    )
    (net (code "23") (name "Net-(BATT1_IC-TIMER1)") (class "Default")
      (node (ref "BATT1_IC") (pin "13") (pinfunction "TIMER1_13") (pintype "bidirectional"))
      (node (ref "C74") (pin "1") (pinfunction "1_1") (pintype "passive"))
    )
    (net (code "24") (name "Net-(BATT1_IC-TIMER2)") (class "Default")
      (node (ref "BATT1_IC") (pin "14") (pinfunction "TIMER2_14") (pintype "bidirectional"))
      (node (ref "C75") (pin "1") (pinfunction "1_1") (pintype "passive"))
    )
    (net (code "25") (name "Net-(BATT1_IC-VADJ)") (class "Default")
      (node (ref "BATT1_IC") (pin "8") (pinfunction "VADJ_8") (pintype "bidirectional"))
      (node (ref "R30") (pin "2") (pinfunction "2_2") (pintype "passive"))
      (node (ref "R31") (pin "2") (pinfunction "2_2") (pintype "passive"))
    )
    (net (code "26") (name "Net-(BATT1_IC-VLO)") (class "Default")
      (node (ref "BATT1_IC") (pin "22") (pinfunction "VLO_22") (pintype "bidirectional"))
      (node (ref "C79") (pin "1") (pinfunction "1_1") (pintype "passive"))
      (node (ref "D1") (pin "A") (pinfunction "A_A") (pintype "passive"))
    )
    (net (code "27") (name "Net-(BATT1_IC-~{FASTCHG})") (class "Default")
      (node (ref "BATT1_IC") (pin "16") (pinfunction "~{FASTCHG}_16") (pintype "bidirectional"))
      (node (ref "R10") (pin "1") (pinfunction "1_1") (pintype "passive"))
      (node (ref "U$7") (pin "P$2") (pinfunction "G_P$2") (pintype "bidirectional"))
    )
    (net (code "28") (name "Net-(BATT1_IC-~{FAULT})") (class "Default")
      (node (ref "BATT1_IC") (pin "15") (pinfunction "~{FAULT}_15") (pintype "bidirectional"))
      (node (ref "R14") (pin "1") (pinfunction "1_1") (pintype "passive"))
      (node (ref "U$9") (pin "P$2") (pinfunction "G_P$2") (pintype "bidirectional"))
    )
    (net (code "29") (name "Net-(BATT1_IC-~{FULLCHG})") (class "Default")
      (node (ref "BATT1_IC") (pin "17") (pinfunction "~{FULLCHG}_17") (pintype "bidirectional"))
      (node (ref "R12") (pin "1") (pinfunction "1_1") (pintype "passive"))
      (node (ref "U$8") (pin "P$2") (pinfunction "G_P$2") (pintype "bidirectional"))
    )
    (net (code "30") (name "Net-(BATT1_IC-~{SHDN})") (class "Default")
      (node (ref "BATT1_IC") (pin "18") (pinfunction "~{SHDN}_18") (pintype "bidirectional"))
      (node (ref "R33") (pin "2") (pinfunction "2_2") (pintype "passive"))
      (node (ref "U$1") (pin "18") (pinfunction "~{SHDN}_18") (pintype "bidirectional"))
      (node (ref "U$56") (pin "P$4") (pinfunction "OUT_P$4") (pintype "bidirectional"))
    )
    (net (code "31") (name "Net-(BATT1_SWITCH-PadP$2)") (class "Default")
      (node (ref "BATT1_SWITCH") (pin "P$2") (pinfunction "P$2_P$2") (pintype "bidirectional"))
      (node (ref "R4") (pin "2") (pinfunction "2_2") (pintype "passive"))
      (node (ref "R6") (pin "2") (pinfunction "2_2") (pintype "passive"))
    )
    (net (code "32") (name "Net-(BATT2_SWITCH-PadP$2)") (class "Default")
      (node (ref "BATT2_SWITCH") (pin "P$2") (pinfunction "P$2_P$2") (pintype "bidirectional"))
      (node (ref "R27") (pin "2") (pinfunction "2_2") (pintype "passive"))
      (node (ref "R8") (pin "2") (pinfunction "2_2") (pintype "passive"))
    )
    (net (code "33") (name "Net-(BUZZER-PadP$1)") (class "Default")
      (node (ref "BUZZER") (pin "P$1") (pinfunction "P$1_P$1") (pintype "bidirectional"))
      (node (ref "R13") (pin "2") (pinfunction "2_2") (pintype "passive"))
      (node (ref "R19") (pin "1") (pinfunction "1_1") (pintype "passive"))
    )
    (net (code "34") (name "Net-(BUZZER2-PadP$1)") (class "Default")
      (node (ref "BUZZER2") (pin "P$1") (pinfunction "P$1_P$1") (pintype "bidirectional"))
      (node (ref "R21") (pin "2") (pinfunction "2_2") (pintype "passive"))
      (node (ref "R22") (pin "1") (pinfunction "1_1") (pintype "passive"))
    )
    (net (code "35") (name "Net-(C5-Pad1)") (class "Default")
      (node (ref "C5") (pin "1") (pinfunction "1_1") (pintype "passive"))
      (node (ref "R3") (pin "1") (pinfunction "1_1") (pintype "passive"))
    )
    (net (code "36") (name "Net-(C70-Pad1)") (class "Default")
      (node (ref "C70") (pin "1") (pinfunction "1_1") (pintype "passive"))
      (node (ref "R32") (pin "1") (pinfunction "1_1") (pintype "passive"))
    )
    (net (code "37") (name "Net-(INPUT-SWITCH-PadP$2)") (class "Default")
      (node (ref "INPUT-SWITCH") (pin "P$2") (pinfunction "P$2_P$2") (pintype "bidirectional"))
      (node (ref "R25") (pin "2") (pinfunction "2_2") (pintype "passive"))
      (node (ref "R26") (pin "2") (pinfunction "2_2") (pintype "passive"))
    )
    (net (code "38") (name "Net-(L1-1)") (class "Default")
      (node (ref "B1-HFET") (pin "SOURCE1") (pinfunction "SOURCE_SOURCE1") (pintype "passive"))
      (node (ref "B1-HFET") (pin "SOURCE2") (pinfunction "SOURCE_SOURCE2") (pintype "passive"))
      (node (ref "B1-HFET") (pin "SOURCE3") (pinfunction "SOURCE_SOURCE3") (pintype "passive"))
      (node (ref "L1") (pin "P$1") (pinfunction "1_P$1") (pintype "passive"))
      (node (ref "U$37") (pin "DRAIN") (pinfunction "DRAIN_DRAIN") (pintype "bidirectional"))
    )
    (net (code "39") (name "Net-(L2-1)") (class "Default")
      (node (ref "L2") (pin "P$1") (pinfunction "1_P$1") (pintype "passive"))
      (node (ref "U$2") (pin "SOURCE1") (pinfunction "SOURCE_SOURCE1") (pintype "passive"))
      (node (ref "U$2") (pin "SOURCE2") (pinfunction "SOURCE_SOURCE2") (pintype "passive"))
      (node (ref "U$2") (pin "SOURCE3") (pinfunction "SOURCE_SOURCE3") (pintype "passive"))
      (node (ref "U$3") (pin "DRAIN") (pinfunction "DRAIN_DRAIN") (pintype "bidirectional"))
    )
    (net (code "40") (name "Net-(L2-2)") (class "Default")
      (node (ref "C17") (pin "1") (pinfunction "1_1") (pintype "passive"))
      (node (ref "L2") (pin "P$2") (pinfunction "2_P$2") (pintype "passive"))
      (node (ref "R5") (pin "2") (pinfunction "2_2") (pintype "passive"))
      (node (ref "R7") (pin "2") (pinfunction "2_2") (pintype "passive"))
      (node (ref "U$1") (pin "19") (pinfunction "CS_19") (pintype "bidirectional"))
    )
    (net (code "41") (name "Net-(LED1-PadA)") (class "Default")
      (node (ref "LED1") (pin "A") (pinfunction "A_A") (pintype "passive"))
      (node (ref "R9") (pin "1") (pinfunction "1_1") (pintype "passive"))
    )
    (net (code "42") (name "Net-(LED2-PadA)") (class "Default")
      (node (ref "LED2") (pin "A") (pinfunction "A_A") (pintype "passive"))
      (node (ref "R11") (pin "1") (pinfunction "1_1") (pintype "passive"))
    )
    (net (code "43") (name "Net-(LED3-PadA)") (class "Default")
      (node (ref "LED3") (pin "A") (pinfunction "A_A") (pintype "passive"))
      (node (ref "R13") (pin "1") (pinfunction "1_1") (pintype "passive"))
    )
    (net (code "44") (name "Net-(LED4-PadA)") (class "Default")
      (node (ref "LED4") (pin "A") (pinfunction "A_A") (pintype "passive"))
      (node (ref "R15") (pin "1") (pinfunction "1_1") (pintype "passive"))
    )
    (net (code "45") (name "Net-(LED5-PadA)") (class "Default")
      (node (ref "LED5") (pin "A") (pinfunction "A_A") (pintype "passive"))
      (node (ref "R17") (pin "1") (pinfunction "1_1") (pintype "passive"))
    )
    (net (code "46") (name "Net-(LED6-PadA)") (class "Default")
      (node (ref "LED6") (pin "A") (pinfunction "A_A") (pintype "passive"))
      (node (ref "R21") (pin "1") (pinfunction "1_1") (pintype "passive"))
    )
    (net (code "47") (name "Net-(LED7-PadA)") (class "Default")
      (node (ref "LED7") (pin "A") (pinfunction "A_A") (pintype "passive"))
      (node (ref "R28") (pin "1") (pinfunction "1_1") (pintype "passive"))
    )
    (net (code "48") (name "Net-(LED8-PadA)") (class "Default")
      (node (ref "LED8") (pin "A") (pinfunction "A_A") (pintype "passive"))
      (node (ref "R33") (pin "1") (pinfunction "1_1") (pintype "passive"))
    )
    (net (code "49") (name "Net-(U$1-BATT)") (class "Default")
      (node (ref "BATT2_FUSE") (pin "P$2") (pinfunction "P$2_P$2") (pintype "bidirectional"))
      (node (ref "C18") (pin "1") (pinfunction "1_1") (pintype "passive"))
      (node (ref "C19") (pin "+") (pinfunction "+_+") (pintype "passive"))
      (node (ref "R5") (pin "1") (pinfunction "1_1") (pintype "passive"))
      (node (ref "R7") (pin "1") (pinfunction "1_1") (pintype "passive"))
      (node (ref "U$1") (pin "7") (pinfunction "BATT_7") (pintype "bidirectional"))
    )
    (net (code "50") (name "Net-(U$1-BST)") (class "Default")
      (node (ref "C13") (pin "2") (pinfunction "2_2") (pintype "passive"))
      (node (ref "D2") (pin "C") (pinfunction "C_C") (pintype "passive"))
      (node (ref "U$1") (pin "23") (pinfunction "BST_23") (pintype "bidirectional"))
    )
    (net (code "51") (name "Net-(U$1-CCI)") (class "Default")
      (node (ref "C7") (pin "1") (pinfunction "1_1") (pintype "passive"))
      (node (ref "U$1") (pin "11") (pinfunction "CCI_11") (pintype "bidirectional"))
    )
    (net (code "52") (name "Net-(U$1-CCS)") (class "Default")
      (node (ref "C8") (pin "1") (pinfunction "1_1") (pintype "passive"))
      (node (ref "U$1") (pin "10") (pinfunction "CCS_10") (pintype "bidirectional"))
    )
    (net (code "53") (name "Net-(U$1-CCV)") (class "Default")
      (node (ref "C6") (pin "1") (pinfunction "1_1") (pintype "passive"))
      (node (ref "R3") (pin "2") (pinfunction "2_2") (pintype "passive"))
      (node (ref "U$1") (pin "9") (pinfunction "CCV_9") (pintype "bidirectional"))
    )
    (net (code "54") (name "Net-(U$1-CELL)") (class "Default")
      (node (ref "C2") (pin "1") (pinfunction "1_1") (pintype "passive"))
      (node (ref "C3") (pin "1") (pinfunction "1_1") (pintype "passive"))
      (node (ref "U$1") (pin "1") (pinfunction "VL_1") (pintype "bidirectional"))
      (node (ref "U$1") (pin "12") (pinfunction "CELL_12") (pintype "bidirectional"))
    )
    (net (code "55") (name "Net-(U$1-CSSN)") (class "Default")
      (node (ref "C1") (pin "1") (pinfunction "1_1") (pintype "passive"))
      (node (ref "U$1") (pin "26") (pinfunction "CSSN_26") (pintype "bidirectional"))
      (node (ref "U$1") (pin "27") (pinfunction "CSSP_27") (pintype "bidirectional"))
      (node (ref "U$1") (pin "28") (pinfunction "DCIN_28") (pintype "bidirectional"))
      (node (ref "U$2") (pin "DRAIN") (pinfunction "DRAIN_DRAIN") (pintype "bidirectional"))
      (node (ref "U$5") (pin "C") (pinfunction "C_C") (pintype "passive"))
    )
    (net (code "56") (name "Net-(U$1-DHI)") (class "Default")
      (node (ref "U$1") (pin "25") (pinfunction "DHI_25") (pintype "bidirectional"))
      (node (ref "U$2") (pin "GATE") (pinfunction "GATE_GATE") (pintype "passive"))
    )
    (net (code "57") (name "Net-(U$1-DLO)") (class "Default")
      (node (ref "U$1") (pin "21") (pinfunction "DLO_21") (pintype "bidirectional"))
      (node (ref "U$3") (pin "GATE") (pinfunction "GATE_GATE") (pintype "passive"))
    )
    (net (code "58") (name "Net-(U$1-ISETIN)") (class "Default")
      (node (ref "C4") (pin "1") (pinfunction "1_1") (pintype "passive"))
      (node (ref "R1") (pin "1") (pinfunction "1_1") (pintype "passive"))
      (node (ref "U$1") (pin "2") (pinfunction "ISETIN_2") (pintype "bidirectional"))
      (node (ref "U$1") (pin "3") (pinfunction "ISETOUT_3") (pintype "bidirectional"))
      (node (ref "U$1") (pin "5") (pinfunction "REF_5") (pintype "bidirectional"))
    )
    (net (code "59") (name "Net-(U$1-LX)") (class "Default")
      (node (ref "C13") (pin "1") (pinfunction "1_1") (pintype "passive"))
      (node (ref "U$1") (pin "24") (pinfunction "LX_24") (pintype "bidirectional"))
    )
    (net (code "60") (name "Net-(U$1-PGND)") (class "Default")
      (node (ref "U$1") (pin "20") (pinfunction "PGND_20") (pintype "bidirectional"))
      (node (ref "U$3") (pin "SOURCE1") (pinfunction "SOURCE_SOURCE1") (pintype "passive"))
      (node (ref "U$3") (pin "SOURCE2") (pinfunction "SOURCE_SOURCE2") (pintype "passive"))
      (node (ref "U$3") (pin "SOURCE3") (pinfunction "SOURCE_SOURCE3") (pintype "passive"))
    )
    (net (code "61") (name "Net-(U$1-THM)") (class "Default")
      (node (ref "U$1") (pin "4") (pinfunction "THM_4") (pintype "bidirectional"))
      (node (ref "U$6") (pin "P$1") (pinfunction "1_P$1") (pintype "passive"))
    )
    (net (code "62") (name "Net-(U$1-TIMER1)") (class "Default")
      (node (ref "C9") (pin "1") (pinfunction "1_1") (pintype "passive"))
      (node (ref "U$1") (pin "13") (pinfunction "TIMER1_13") (pintype "bidirectional"))
    )
    (net (code "63") (name "Net-(U$1-TIMER2)") (class "Default")
      (node (ref "C10") (pin "1") (pinfunction "1_1") (pintype "passive"))
      (node (ref "U$1") (pin "14") (pinfunction "TIMER2_14") (pintype "bidirectional"))
    )
    (net (code "64") (name "Net-(U$1-VADJ)") (class "Default")
      (node (ref "R1") (pin "2") (pinfunction "2_2") (pintype "passive"))
      (node (ref "R2") (pin "2") (pinfunction "2_2") (pintype "passive"))
      (node (ref "U$1") (pin "8") (pinfunction "VADJ_8") (pintype "bidirectional"))
    )
    (net (code "65") (name "Net-(U$1-VLO)") (class "Default")
      (node (ref "C14") (pin "1") (pinfunction "1_1") (pintype "passive"))
      (node (ref "D2") (pin "A") (pinfunction "A_A") (pintype "passive"))
      (node (ref "U$1") (pin "22") (pinfunction "VLO_22") (pintype "bidirectional"))
    )
    (net (code "66") (name "Net-(U$1-~{FASTCHG})") (class "Default")
      (node (ref "R16") (pin "1") (pinfunction "1_1") (pintype "passive"))
      (node (ref "U$1") (pin "16") (pinfunction "~{FASTCHG}_16") (pintype "bidirectional"))
      (node (ref "U$10") (pin "P$2") (pinfunction "G_P$2") (pintype "bidirectional"))
    )
    (net (code "67") (name "Net-(U$1-~{FAULT})") (class "Default")
      (node (ref "R20") (pin "1") (pinfunction "1_1") (pintype "passive"))
      (node (ref "U$1") (pin "15") (pinfunction "~{FAULT}_15") (pintype "bidirectional"))
      (node (ref "U$12") (pin "P$2") (pinfunction "G_P$2") (pintype "bidirectional"))
    )
    (net (code "68") (name "Net-(U$1-~{FULLCHG})") (class "Default")
      (node (ref "R18") (pin "1") (pinfunction "1_1") (pintype "passive"))
      (node (ref "U$1") (pin "17") (pinfunction "~{FULLCHG}_17") (pintype "bidirectional"))
      (node (ref "U$11") (pin "P$2") (pinfunction "G_P$2") (pintype "bidirectional"))
    )
    (net (code "69") (name "Net-(U$7-D)") (class "Default")
      (node (ref "R9") (pin "2") (pinfunction "2_2") (pintype "passive"))
      (node (ref "U$7") (pin "P$3") (pinfunction "D_P$3") (pintype "bidirectional"))
    )
    (net (code "70") (name "Net-(U$8-D)") (class "Default")
      (node (ref "R11") (pin "2") (pinfunction "2_2") (pintype "passive"))
      (node (ref "U$8") (pin "P$3") (pinfunction "D_P$3") (pintype "bidirectional"))
    )
    (net (code "71") (name "Net-(U$9-D)") (class "Default")
      (node (ref "R19") (pin "2") (pinfunction "2_2") (pintype "passive"))
      (node (ref "U$9") (pin "P$3") (pinfunction "D_P$3") (pintype "bidirectional"))
    )
    (net (code "72") (name "Net-(U$10-D)") (class "Default")
      (node (ref "R15") (pin "2") (pinfunction "2_2") (pintype "passive"))
      (node (ref "U$10") (pin "P$3") (pinfunction "D_P$3") (pintype "bidirectional"))
    )
    (net (code "73") (name "Net-(U$11-D)") (class "Default")
      (node (ref "R17") (pin "2") (pinfunction "2_2") (pintype "passive"))
      (node (ref "U$11") (pin "P$3") (pinfunction "D_P$3") (pintype "bidirectional"))
    )
    (net (code "74") (name "Net-(U$12-D)") (class "Default")
      (node (ref "R22") (pin "2") (pinfunction "2_2") (pintype "passive"))
      (node (ref "U$12") (pin "P$3") (pinfunction "D_P$3") (pintype "bidirectional"))
    )
    (net (code "75") (name "Net-(U$16-G)") (class "Default")
      (node (ref "C11") (pin "1") (pinfunction "1_1") (pintype "passive"))
      (node (ref "R4") (pin "1") (pinfunction "1_1") (pintype "passive"))
      (node (ref "U$16") (pin "1") (pinfunction "G_1") (pintype "passive"))
    )
    (net (code "76") (name "Net-(U$16-S)") (class "Default")
      (node (ref "BATT1_FUSE") (pin "P$1") (pinfunction "P$1_P$1") (pintype "bidirectional"))
      (node (ref "U$16") (pin "3") (pinfunction "S_3") (pintype "passive"))
    )
    (net (code "77") (name "Net-(U$19-G)") (class "Default")
      (node (ref "C20") (pin "1") (pinfunction "1_1") (pintype "passive"))
      (node (ref "R25") (pin "1") (pinfunction "1_1") (pintype "passive"))
      (node (ref "U$19") (pin "1") (pinfunction "G_1") (pintype "passive"))
    )
    (net (code "78") (name "Net-(U$23-G)") (class "Default")
      (node (ref "C12") (pin "1") (pinfunction "1_1") (pintype "passive"))
      (node (ref "R8") (pin "1") (pinfunction "1_1") (pintype "passive"))
      (node (ref "U$23") (pin "1") (pinfunction "G_1") (pintype "passive"))
    )
    (net (code "79") (name "Net-(U$23-S)") (class "Default")
      (node (ref "BATT2_FUSE") (pin "P$1") (pinfunction "P$1_P$1") (pintype "bidirectional"))
      (node (ref "U$23") (pin "3") (pinfunction "S_3") (pintype "passive"))
    )
    (net (code "80") (name "Net-(U$56-IN)") (class "Default")
      (node (ref "C60") (pin "1") (pinfunction "1_1") (pintype "passive"))
      (node (ref "R23") (pin "2") (pinfunction "2_2") (pintype "passive"))
      (node (ref "U$56") (pin "P$2") (pinfunction "IN_P$2") (pintype "bidirectional"))
    )
    (net (code "81") (name "Net-(U$56-VDD)") (class "Default")
      (node (ref "C62") (pin "1") (pinfunction "1_1") (pintype "passive"))
      (node (ref "R24") (pin "2") (pinfunction "2_2") (pintype "passive"))
      (node (ref "U$56") (pin "P$5") (pinfunction "VDD_P$5") (pintype "bidirectional"))
      (node (ref "U$57") (pin "P$2") (pinfunction "VOUT_P$2") (pintype "bidirectional"))
      (node (ref "U$57") (pin "P$4") (pinfunction "VOUT_P$4") (pintype "bidirectional"))
    )
  )
)
